# KKK_valdiklis.net
KiCad netlist of a schematic drawn in EAGLE
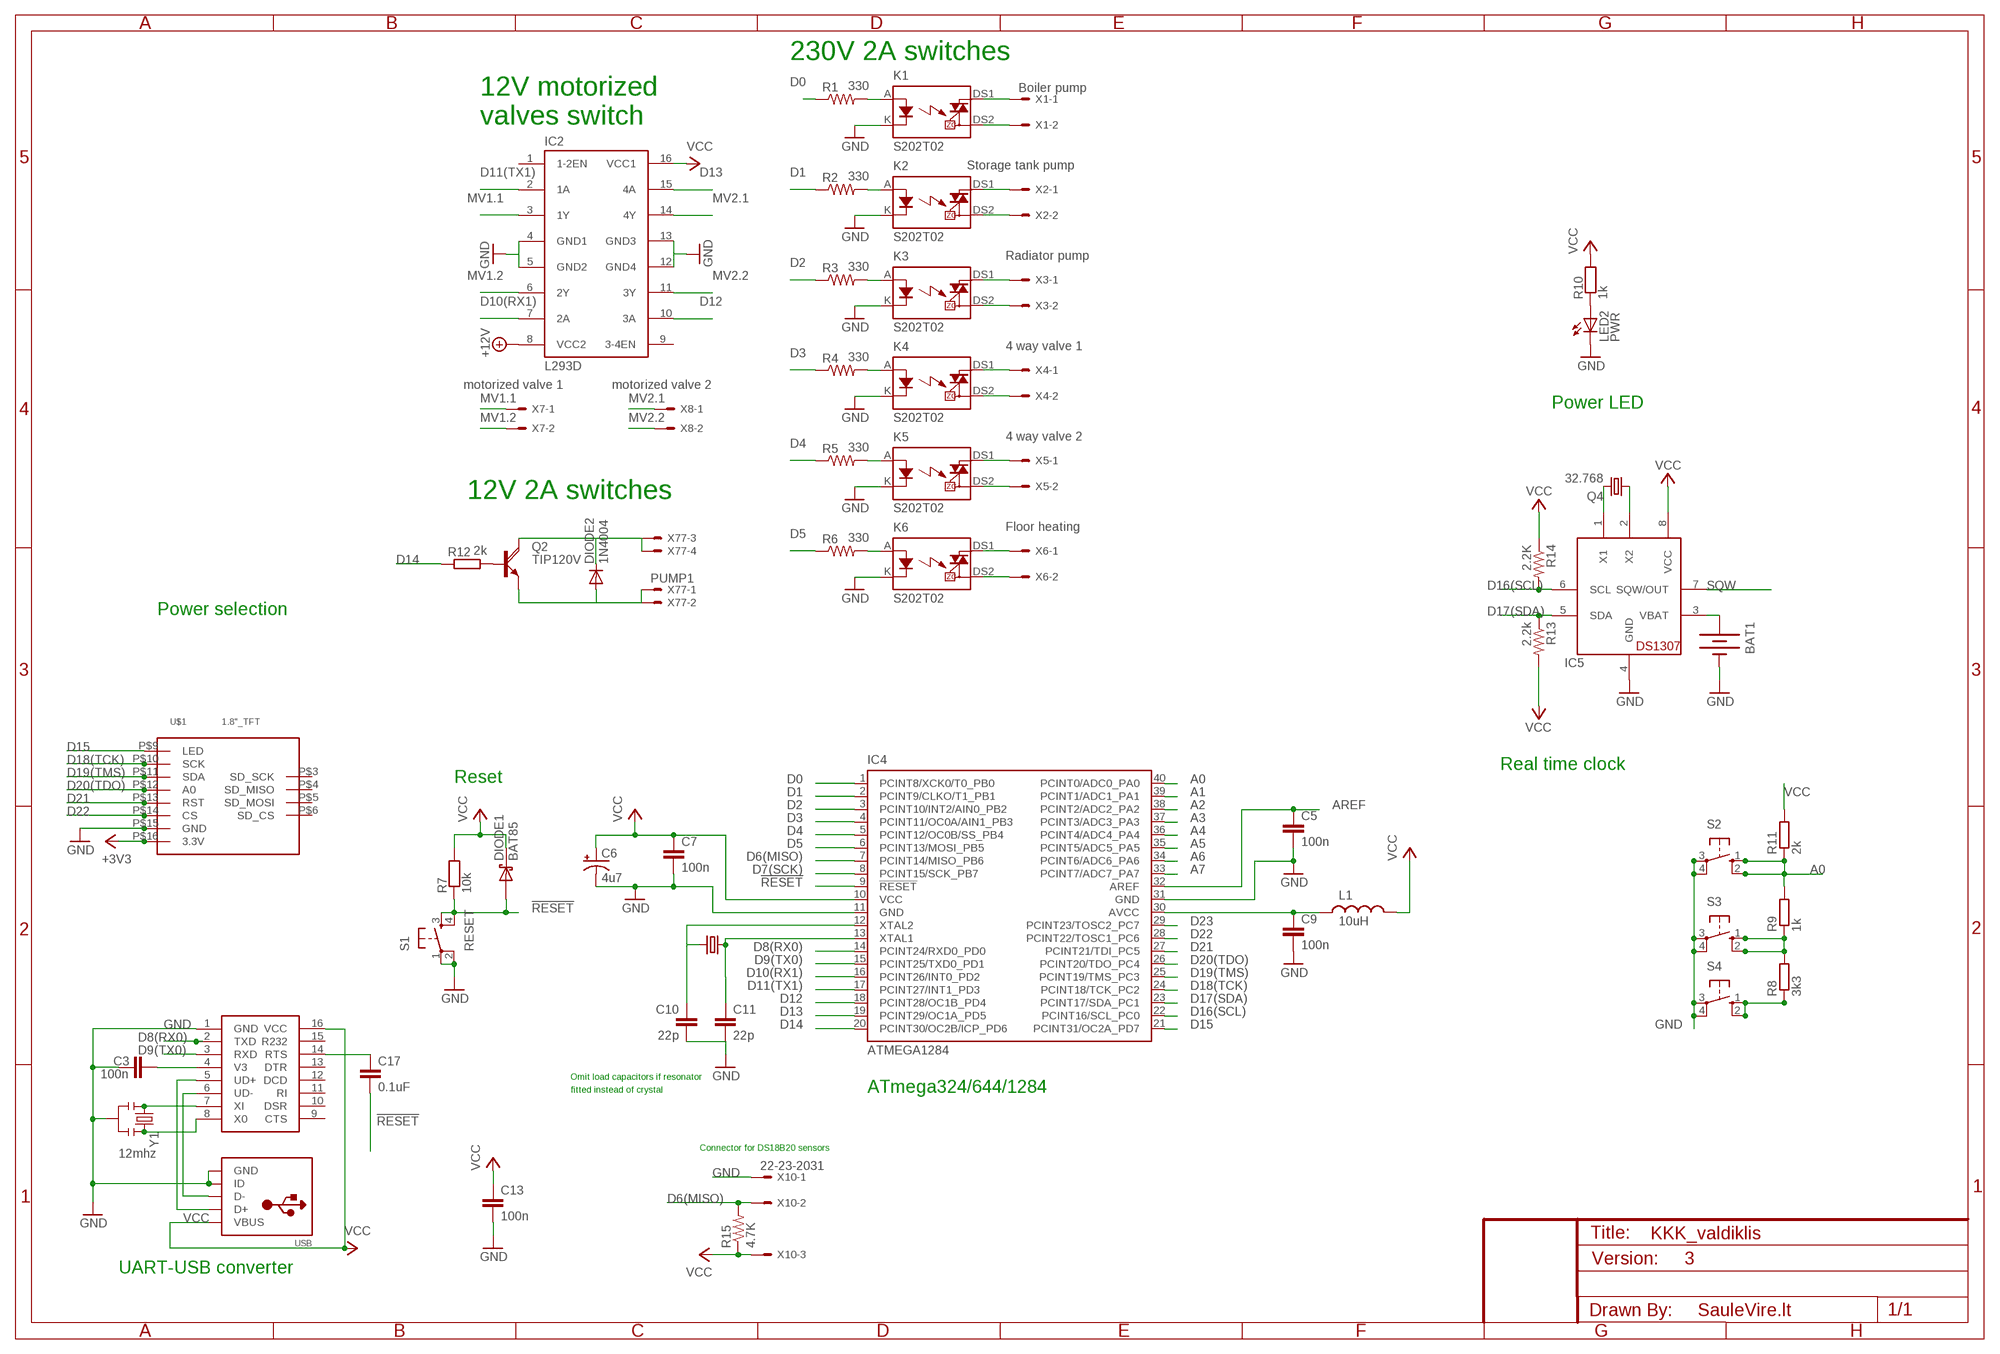
[diagram p0: schematic, sheet 1]

(export (version "E")
  (design (tool "Eeschema 10.0.6"))
  (components
    (comp (ref "BAT1")
      (value "BATTERY20PTH")
      (footprint "eagle-import:BATTCOM_20MM_PTH")
      (libsource (lib "eagle-import") (part "BATTERY20PTH"))
    )
    (comp (ref "C3")
      (value "100n")
      (footprint "eagle-import:CAP-PTH-SMALL")
      (libsource (lib "eagle-import") (part "CAPPTH"))
    )
    (comp (ref "C5")
      (value "100n")
      (footprint "eagle-import:CAP-PTH-SMALL")
      (libsource (lib "eagle-import") (part "CAPPTH"))
    )
    (comp (ref "C6")
      (value "4u7")
      (footprint "eagle-import:CPOL-RADIAL-10UF-25V")
      (libsource (lib "eagle-import") (part "CAP_POLPTH2"))
    )
    (comp (ref "C7")
      (value "100n")
      (footprint "eagle-import:CAP-PTH-SMALL")
      (libsource (lib "eagle-import") (part "CAPPTH"))
    )
    (comp (ref "C9")
      (value "100n")
      (footprint "eagle-import:CAP-PTH-SMALL")
      (libsource (lib "eagle-import") (part "CAPPTH"))
    )
    (comp (ref "C10")
      (value "22p")
      (footprint "eagle-import:CAP-PTH-SMALL")
      (libsource (lib "eagle-import") (part "CAPPTH"))
    )
    (comp (ref "C11")
      (value "22p")
      (footprint "eagle-import:CAP-PTH-SMALL")
      (libsource (lib "eagle-import") (part "CAPPTH"))
    )
    (comp (ref "C13")
      (value "100n")
      (footprint "eagle-import:CAP-PTH-SMALL")
      (libsource (lib "eagle-import") (part "CAPPTH"))
    )
    (comp (ref "C17")
      (value "0.1uF")
      (footprint "eagle-import:C025-024X044")
      (libsource (lib "eagle-import") (part "C-EU025-024X044"))
    )
    (comp (ref "DIODE1")
      (value "BAT85")
      (footprint "eagle-import:DIODE-TH-0.4")
      (libsource (lib "eagle-import") (part "DIODE-SCHOTTKY"))
    )
    (comp (ref "DIODE2")
      (value "1N4004")
      (footprint "eagle-import:DO41-10")
      (libsource (lib "eagle-import") (part "1N4004"))
    )
    (comp (ref "IC2")
      (value "L293D")
      (footprint "eagle-import:DIL16")
      (libsource (lib "eagle-import") (part "L293D"))
    )
    (comp (ref "IC4")
      (value "ATMEGA1284")
      (footprint "eagle-import:DIL40")
      (fields (field (name "MPN") "ATMEGA644-20PU"))
      (libsource (lib "eagle-import") (part "ATMEGA644-PU20"))
    )
    (comp (ref "IC5")
      (value "DS1307")
      (footprint "eagle-import:DIL08")
      (libsource (lib "eagle-import") (part "DS1307"))
    )
    (comp (ref "K1")
      (value "S202T02")
      (footprint "eagle-import:S202T02")
      (libsource (lib "eagle-import") (part "S202T02"))
    )
    (comp (ref "K2")
      (value "S202T02")
      (footprint "eagle-import:S202T02")
      (libsource (lib "eagle-import") (part "S202T02"))
    )
    (comp (ref "K3")
      (value "S202T02")
      (footprint "eagle-import:S202T02")
      (libsource (lib "eagle-import") (part "S202T02"))
    )
    (comp (ref "K4")
      (value "S202T02")
      (footprint "eagle-import:S202T02")
      (libsource (lib "eagle-import") (part "S202T02"))
    )
    (comp (ref "K5")
      (value "S202T02")
      (footprint "eagle-import:S202T02")
      (libsource (lib "eagle-import") (part "S202T02"))
    )
    (comp (ref "K6")
      (value "S202T02")
      (footprint "eagle-import:S202T02")
      (libsource (lib "eagle-import") (part "S202T02"))
    )
    (comp (ref "L1")
      (value "10uH")
      (footprint "eagle-import:RES-AXIAL-0.4")
      (libsource (lib "eagle-import") (part "INDUCTOR0.4{dblquote}-AXIAL"))
    )
    (comp (ref "LED2")
      (value "PWR")
      (footprint "eagle-import:LED3MM")
      (libsource (lib "eagle-import") (part "LED3MM"))
    )
    (comp (ref "Q2")
      (value "TIP120V")
      (footprint "eagle-import:TO220AV")
      (libsource (lib "eagle-import") (part "TIP120V"))
    )
    (comp (ref "Q4")
      (value "32.768")
      (footprint "eagle-import:TC38H")
      (libsource (lib "eagle-import") (part "CRYTALTC38H"))
    )
    (comp (ref "R1")
      (value "330")
      (footprint "eagle-import:0207_10")
      (libsource (lib "eagle-import") (part "resistor-1_R-US_0207/10"))
    )
    (comp (ref "R2")
      (value "330")
      (footprint "eagle-import:0207_10")
      (libsource (lib "eagle-import") (part "resistor-1_R-US_0207/10"))
    )
    (comp (ref "R3")
      (value "330")
      (footprint "eagle-import:0207_10")
      (libsource (lib "eagle-import") (part "resistor-1_R-US_0207/10"))
    )
    (comp (ref "R4")
      (value "330")
      (footprint "eagle-import:0207_10")
      (libsource (lib "eagle-import") (part "resistor-1_R-US_0207/10"))
    )
    (comp (ref "R5")
      (value "330")
      (footprint "eagle-import:0207_10")
      (libsource (lib "eagle-import") (part "resistor-1_R-US_0207/10"))
    )
    (comp (ref "R6")
      (value "330")
      (footprint "eagle-import:0207_10")
      (libsource (lib "eagle-import") (part "resistor-1_R-US_0207/10"))
    )
    (comp (ref "R7")
      (value "10k")
      (footprint "eagle-import:RES-AXIAL-0.4")
      (libsource (lib "eagle-import") (part "RESISTOR"))
    )
    (comp (ref "R8")
      (value "3k3")
      (footprint "eagle-import:0207_10")
      (libsource (lib "eagle-import") (part "R-EU_0207/10"))
    )
    (comp (ref "R9")
      (value "1k")
      (footprint "eagle-import:0207_10")
      (libsource (lib "eagle-import") (part "R-EU_0207/10"))
    )
    (comp (ref "R10")
      (value "1k")
      (footprint "eagle-import:RES-AXIAL-0.4")
      (libsource (lib "eagle-import") (part "RESISTOR"))
    )
    (comp (ref "R11")
      (value "2k")
      (footprint "eagle-import:0207_10")
      (libsource (lib "eagle-import") (part "R-EU_0207/10"))
    )
    (comp (ref "R12")
      (value "2k")
      (footprint "eagle-import:0207_10")
      (libsource (lib "eagle-import") (part "R-EU_0207/10"))
    )
    (comp (ref "R13")
      (value "2.2k")
      (footprint "eagle-import:0207_10")
      (libsource (lib "eagle-import") (part "R-US_0207/10"))
    )
    (comp (ref "R14")
      (value "2.2K")
      (footprint "eagle-import:0207_10")
      (libsource (lib "eagle-import") (part "R-US_0207/10"))
    )
    (comp (ref "R15")
      (value "4.7K")
      (footprint "eagle-import:0207_10")
      (libsource (lib "eagle-import") (part "R-US_0207/10"))
    )
    (comp (ref "S1")
      (value "RESET")
      (footprint "eagle-import:TACTILE-PTH")
      (libsource (lib "eagle-import") (part "TAC_SWITCHPTH"))
    )
    (comp (ref "S2")
      (value "10-XX")
      (footprint "eagle-import:B3F-10XX")
      (fields (field (name "MPN") "B3F-1000"))
      (libsource (lib "eagle-import") (part "10-XX"))
    )
    (comp (ref "S3")
      (value "10-XX")
      (footprint "eagle-import:B3F-10XX")
      (fields (field (name "MPN") "B3F-1000"))
      (libsource (lib "eagle-import") (part "10-XX"))
    )
    (comp (ref "S4")
      (value "10-XX")
      (footprint "eagle-import:B3F-10XX")
      (fields (field (name "MPN") "B3F-1000"))
      (libsource (lib "eagle-import") (part "10-XX"))
    )
    (comp (ref "U$1")
      (value "1.8\"_TFT")
      (footprint "eagle-import:1.8__TFT")
      (libsource (lib "eagle-import") (part "1.8{dblquote}_TFT"))
    )
    (comp (ref "U$2")
      (value "CH340G")
      (footprint "eagle-import:SO016")
      (libsource (lib "eagle-import") (part "CH340G"))
    )
    (comp (ref "USB")
      (value "USBMOLEX")
      (footprint "eagle-import:USB-MINIB-THM-MOLEX")
      (libsource (lib "eagle-import") (part "USBMOLEX"))
    )
    (comp (ref "X1")
      (value "Boiler pump")
      (footprint "eagle-import:22-23-2021")
      (fields (field (name "MF") "MOLEX") (field (name "MPN") "22-23-2021"))
      (libsource (lib "eagle-import") (part "22-23-2021"))
    )
    (comp (ref "X2")
      (value "Storage tank pump")
      (footprint "eagle-import:22-23-2021")
      (fields (field (name "MF") "MOLEX") (field (name "MPN") "22-23-2021"))
      (libsource (lib "eagle-import") (part "22-23-2021"))
    )
    (comp (ref "X3")
      (value "Radiator pump")
      (footprint "eagle-import:22-23-2021")
      (fields (field (name "MF") "MOLEX") (field (name "MPN") "22-23-2021"))
      (libsource (lib "eagle-import") (part "22-23-2021"))
    )
    (comp (ref "X4")
      (value "4 way valve 1")
      (footprint "eagle-import:22-23-2021")
      (fields (field (name "MF") "MOLEX") (field (name "MPN") "22-23-2021"))
      (libsource (lib "eagle-import") (part "22-23-2021"))
    )
    (comp (ref "X5")
      (value "4 way valve 2")
      (footprint "eagle-import:22-23-2021")
      (fields (field (name "MF") "MOLEX") (field (name "MPN") "22-23-2021"))
      (libsource (lib "eagle-import") (part "22-23-2021"))
    )
    (comp (ref "X6")
      (value "Floor heating")
      (footprint "eagle-import:22-23-2021")
      (fields (field (name "MF") "MOLEX") (field (name "MPN") "22-23-2021"))
      (libsource (lib "eagle-import") (part "22-23-2021"))
    )
    (comp (ref "X7")
      (value "motorized valve 1")
      (footprint "eagle-import:22-23-2021")
      (fields (field (name "MF") "MOLEX") (field (name "MPN") "22-23-2021"))
      (libsource (lib "eagle-import") (part "22-23-2021"))
    )
    (comp (ref "X8")
      (value "motorized valve 2")
      (footprint "eagle-import:22-23-2021")
      (fields (field (name "MF") "MOLEX") (field (name "MPN") "22-23-2021"))
      (libsource (lib "eagle-import") (part "22-23-2021"))
    )
    (comp (ref "X9")
      (value "16MHz")
      (footprint "eagle-import:HC49US")
      (libsource (lib "eagle-import") (part "CRYSTALHC49US"))
    )
    (comp (ref "X10")
      (value "22-23-2031")
      (footprint "eagle-import:22-23-2031")
      (fields (field (name "MF") "MOLEX"))
      (libsource (lib "eagle-import") (part "22-23-2031"))
    )
    (comp (ref "X77")
      (value "PUMP1")
      (footprint "eagle-import:22-23-2041")
      (fields (field (name "MF") "MOLEX") (field (name "MPN") "22-23-2041"))
      (libsource (lib "eagle-import") (part "22-23-2041"))
    )
    (comp (ref "Y1")
      (value "12mhz")
      (footprint "eagle-import:RESONATOR-PTH")
      (libsource (lib "eagle-import") (part "RESONATORPTH"))
    )
  )
  (nets
    (net (code "1") (name "+3V3") (class "Default")
      (node (ref "U$1") (pin "P$16") (pinfunction "3.3V_P$16") (pintype "bidirectional"))
    )
    (net (code "2") (name "+12V") (class "Default")
      (node (ref "IC2") (pin "8") (pinfunction "VCC2_8") (pintype "power_in"))
    )
    (net (code "3") (name "/A0") (class "Default")
      (node (ref "IC4") (pin "40") (pinfunction "PCINT0/ADC0_PA0_40") (pintype "bidirectional"))
      (node (ref "R11") (pin "1") (pinfunction "1_1") (pintype "passive"))
      (node (ref "R9") (pin "2") (pinfunction "2_2") (pintype "passive"))
      (node (ref "S2") (pin "1") (pinfunction "S_1") (pintype "passive"))
      (node (ref "S2") (pin "2") (pinfunction "S1_2") (pintype "passive"))
    )
    (net (code "4") (name "/A1") (class "Default")
      (node (ref "IC4") (pin "39") (pinfunction "PCINT1/ADC1_PA1_39") (pintype "bidirectional"))
    )
    (net (code "5") (name "/A2") (class "Default")
      (node (ref "IC4") (pin "38") (pinfunction "PCINT2/ADC2_PA2_38") (pintype "bidirectional"))
    )
    (net (code "6") (name "/A3") (class "Default")
      (node (ref "IC4") (pin "37") (pinfunction "PCINT3/ADC3_PA3_37") (pintype "bidirectional"))
    )
    (net (code "7") (name "/A4") (class "Default")
      (node (ref "IC4") (pin "36") (pinfunction "PCINT4/ADC4_PA4_36") (pintype "bidirectional"))
    )
    (net (code "8") (name "/A5") (class "Default")
      (node (ref "IC4") (pin "35") (pinfunction "PCINT5/ADC5_PA5_35") (pintype "bidirectional"))
    )
    (net (code "9") (name "/A6") (class "Default")
      (node (ref "IC4") (pin "34") (pinfunction "PCINT6/ADC6_PA6_34") (pintype "bidirectional"))
    )
    (net (code "10") (name "/A7") (class "Default")
      (node (ref "IC4") (pin "33") (pinfunction "PCINT7/ADC7_PA7_33") (pintype "bidirectional"))
    )
    (net (code "11") (name "/AREF") (class "Default")
      (node (ref "C5") (pin "1") (pinfunction "1_1") (pintype "passive"))
      (node (ref "IC4") (pin "32") (pinfunction "AREF_32") (pintype "passive"))
    )
    (net (code "12") (name "/D0") (class "Default")
      (node (ref "IC4") (pin "1") (pinfunction "PCINT8/XCK0/T0_PB0_1") (pintype "bidirectional"))
      (node (ref "R1") (pin "1") (pinfunction "1_1") (pintype "passive"))
    )
    (net (code "13") (name "/D1") (class "Default")
      (node (ref "IC4") (pin "2") (pinfunction "PCINT9/CLKO/T1_PB1_2") (pintype "bidirectional"))
      (node (ref "R2") (pin "1") (pinfunction "1_1") (pintype "passive"))
    )
    (net (code "14") (name "/D2") (class "Default")
      (node (ref "IC4") (pin "3") (pinfunction "PCINT10/INT2/AIN0_PB2_3") (pintype "bidirectional"))
      (node (ref "R3") (pin "1") (pinfunction "1_1") (pintype "passive"))
    )
    (net (code "15") (name "/D3") (class "Default")
      (node (ref "IC4") (pin "4") (pinfunction "PCINT11/OC0A/AIN1_PB3_4") (pintype "bidirectional"))
      (node (ref "R4") (pin "1") (pinfunction "1_1") (pintype "passive"))
    )
    (net (code "16") (name "/D4") (class "Default")
      (node (ref "IC4") (pin "5") (pinfunction "PCINT12/OC0B/SS_PB4_5") (pintype "bidirectional"))
      (node (ref "R5") (pin "1") (pinfunction "1_1") (pintype "passive"))
    )
    (net (code "17") (name "/D5") (class "Default")
      (node (ref "IC4") (pin "6") (pinfunction "PCINT13/MOSI_PB5_6") (pintype "bidirectional"))
      (node (ref "R6") (pin "1") (pinfunction "1_1") (pintype "passive"))
    )
    (net (code "18") (name "/D6(MISO)") (class "Default")
      (node (ref "IC4") (pin "7") (pinfunction "PCINT14/MISO_PB6_7") (pintype "bidirectional"))
      (node (ref "R15") (pin "2") (pinfunction "2_2") (pintype "passive"))
      (node (ref "X10") (pin "2") (pinfunction "S_2") (pintype "passive"))
    )
    (net (code "19") (name "/D7(SCK)") (class "Default")
      (node (ref "IC4") (pin "8") (pinfunction "PCINT15/SCK_PB7_8") (pintype "bidirectional"))
    )
    (net (code "20") (name "/D8(RX0)") (class "Default")
      (node (ref "IC4") (pin "14") (pinfunction "PCINT24/RXD0_PD0_14") (pintype "bidirectional"))
      (node (ref "U$2") (pin "2") (pinfunction "TXD_2") (pintype "bidirectional"))
    )
    (net (code "21") (name "/D9(TX0)") (class "Default")
      (node (ref "IC4") (pin "15") (pinfunction "PCINT25/TXD0_PD1_15") (pintype "bidirectional"))
      (node (ref "U$2") (pin "3") (pinfunction "RXD_3") (pintype "bidirectional"))
    )
    (net (code "22") (name "/D10(RX1)") (class "Default")
      (node (ref "IC2") (pin "7") (pinfunction "2A_7") (pintype "input"))
      (node (ref "IC4") (pin "16") (pinfunction "PCINT26/INT0_PD2_16") (pintype "bidirectional"))
    )
    (net (code "23") (name "/D11(TX1)") (class "Default")
      (node (ref "IC2") (pin "2") (pinfunction "1A_2") (pintype "input"))
      (node (ref "IC4") (pin "17") (pinfunction "PCINT27/INT1_PD3_17") (pintype "bidirectional"))
    )
    (net (code "24") (name "/D12") (class "Default")
      (node (ref "IC2") (pin "10") (pinfunction "3A_10") (pintype "input"))
      (node (ref "IC4") (pin "18") (pinfunction "PCINT28/OC1B_PD4_18") (pintype "bidirectional"))
    )
    (net (code "25") (name "/D13") (class "Default")
      (node (ref "IC2") (pin "15") (pinfunction "4A_15") (pintype "input"))
      (node (ref "IC4") (pin "19") (pinfunction "PCINT29/OC1A_PD5_19") (pintype "bidirectional"))
    )
    (net (code "26") (name "/D14") (class "Default")
      (node (ref "IC4") (pin "20") (pinfunction "PCINT30/OC2B/ICP_PD6_20") (pintype "bidirectional"))
      (node (ref "R12") (pin "1") (pinfunction "1_1") (pintype "passive"))
    )
    (net (code "27") (name "/D15") (class "Default")
      (node (ref "IC4") (pin "21") (pinfunction "PCINT31/OC2A_PD7_21") (pintype "bidirectional"))
      (node (ref "U$1") (pin "P$9") (pinfunction "LED_P$9") (pintype "bidirectional"))
    )
    (net (code "28") (name "/D16(SCL)") (class "Default")
      (node (ref "IC4") (pin "22") (pinfunction "PCINT16/SCL_PC0_22") (pintype "bidirectional"))
      (node (ref "IC5") (pin "6") (pinfunction "SCL_6") (pintype "bidirectional"))
      (node (ref "R14") (pin "2") (pinfunction "2_2") (pintype "passive"))
    )
    (net (code "29") (name "/D17(SDA)") (class "Default")
      (node (ref "IC4") (pin "23") (pinfunction "PCINT17/SDA_PC1_23") (pintype "bidirectional"))
      (node (ref "IC5") (pin "5") (pinfunction "SDA_5") (pintype "bidirectional"))
      (node (ref "R13") (pin "1") (pinfunction "1_1") (pintype "passive"))
    )
    (net (code "30") (name "/D18(TCK)") (class "Default")
      (node (ref "IC4") (pin "24") (pinfunction "PCINT18/TCK_PC2_24") (pintype "bidirectional"))
      (node (ref "U$1") (pin "P$10") (pinfunction "SCK_P$10") (pintype "bidirectional"))
    )
    (net (code "31") (name "/D19(TMS)") (class "Default")
      (node (ref "IC4") (pin "25") (pinfunction "PCINT19/TMS_PC3_25") (pintype "bidirectional"))
      (node (ref "U$1") (pin "P$11") (pinfunction "SDA_P$11") (pintype "bidirectional"))
    )
    (net (code "32") (name "/D20(TDO)") (class "Default")
      (node (ref "IC4") (pin "26") (pinfunction "PCINT20/TDO_PC4_26") (pintype "bidirectional"))
      (node (ref "U$1") (pin "P$12") (pinfunction "A0_P$12") (pintype "bidirectional"))
    )
    (net (code "33") (name "/D21") (class "Default")
      (node (ref "IC4") (pin "27") (pinfunction "PCINT21/TDI_PC5_27") (pintype "bidirectional"))
      (node (ref "U$1") (pin "P$13") (pinfunction "RST_P$13") (pintype "bidirectional"))
    )
    (net (code "34") (name "/D22") (class "Default")
      (node (ref "IC4") (pin "28") (pinfunction "PCINT22/TOSC1_PC6_28") (pintype "bidirectional"))
      (node (ref "U$1") (pin "P$14") (pinfunction "CS_P$14") (pintype "bidirectional"))
    )
    (net (code "35") (name "/D23") (class "Default")
      (node (ref "IC4") (pin "29") (pinfunction "PCINT23/TOSC2_PC7_29") (pintype "bidirectional"))
    )
    (net (code "36") (name "/MV1.1") (class "Default")
      (node (ref "IC2") (pin "3") (pinfunction "1Y_3") (pintype "output"))
      (node (ref "X7") (pin "1") (pinfunction "S_1") (pintype "passive"))
    )
    (net (code "37") (name "/MV1.2") (class "Default")
      (node (ref "IC2") (pin "6") (pinfunction "2Y_6") (pintype "output"))
      (node (ref "X7") (pin "2") (pinfunction "S_2") (pintype "passive"))
    )
    (net (code "38") (name "/MV2.1") (class "Default")
      (node (ref "IC2") (pin "14") (pinfunction "4Y_14") (pintype "output"))
      (node (ref "X8") (pin "1") (pinfunction "S_1") (pintype "passive"))
    )
    (net (code "39") (name "/MV2.2") (class "Default")
      (node (ref "IC2") (pin "11") (pinfunction "3Y_11") (pintype "output"))
      (node (ref "X8") (pin "2") (pinfunction "S_2") (pintype "passive"))
    )
    (net (code "40") (name "/SQW") (class "Default")
      (node (ref "IC5") (pin "7") (pinfunction "SQW/OUT_7") (pintype "bidirectional"))
    )
    (net (code "41") (name "/~{RESET}") (class "Default")
      (node (ref "C17") (pin "2") (pinfunction "2_2") (pintype "passive"))
      (node (ref "DIODE1") (pin "A") (pinfunction "A_A") (pintype "passive"))
      (node (ref "IC4") (pin "9") (pinfunction "~{RESET}_9") (pintype "input"))
      (node (ref "R7") (pin "P$1") (pinfunction "1_P$1") (pintype "passive"))
      (node (ref "S1") (pin "3") (pinfunction "3_3") (pintype "passive"))
      (node (ref "S1") (pin "4") (pinfunction "4_4") (pintype "passive"))
    )
    (net (code "42") (name "GND") (class "Default")
      (node (ref "BAT1") (pin "2") (pinfunction "-_2") (pintype "power_in"))
      (node (ref "C10") (pin "2") (pinfunction "2_2") (pintype "passive"))
      (node (ref "C11") (pin "2") (pinfunction "2_2") (pintype "passive"))
      (node (ref "C13") (pin "2") (pinfunction "2_2") (pintype "passive"))
      (node (ref "C3") (pin "1") (pinfunction "1_1") (pintype "passive"))
      (node (ref "C5") (pin "2") (pinfunction "2_2") (pintype "passive"))
      (node (ref "C6") (pin "2") (pinfunction "-_2") (pintype "passive"))
      (node (ref "C7") (pin "2") (pinfunction "2_2") (pintype "passive"))
      (node (ref "C9") (pin "2") (pinfunction "2_2") (pintype "passive"))
      (node (ref "DIODE2") (pin "A") (pinfunction "A_A") (pintype "passive"))
      (node (ref "IC2") (pin "12") (pinfunction "GND4_12") (pintype "power_in"))
      (node (ref "IC2") (pin "13") (pinfunction "GND3_13") (pintype "power_in"))
      (node (ref "IC2") (pin "4") (pinfunction "GND1_4") (pintype "power_in"))
      (node (ref "IC2") (pin "5") (pinfunction "GND2_5") (pintype "power_in"))
      (node (ref "IC4") (pin "11") (pinfunction "GND_11") (pintype "power_in"))
      (node (ref "IC4") (pin "31") (pinfunction "GND_31") (pintype "power_in"))
      (node (ref "IC5") (pin "4") (pinfunction "GND_4") (pintype "power_in"))
      (node (ref "K1") (pin "K") (pinfunction "K_K") (pintype "passive"))
      (node (ref "K2") (pin "K") (pinfunction "K_K") (pintype "passive"))
      (node (ref "K3") (pin "K") (pinfunction "K_K") (pintype "passive"))
      (node (ref "K4") (pin "K") (pinfunction "K_K") (pintype "passive"))
      (node (ref "K5") (pin "K") (pinfunction "K_K") (pintype "passive"))
      (node (ref "K6") (pin "K") (pinfunction "K_K") (pintype "passive"))
      (node (ref "LED2") (pin "K") (pinfunction "C_K") (pintype "passive"))
      (node (ref "Q2") (pin "E") (pinfunction "E_E") (pintype "passive"))
      (node (ref "S1") (pin "1") (pinfunction "1_1") (pintype "passive"))
      (node (ref "S1") (pin "2") (pinfunction "2_2") (pintype "passive"))
      (node (ref "S2") (pin "3") (pinfunction "P_3") (pintype "passive"))
      (node (ref "S2") (pin "4") (pinfunction "P1_4") (pintype "passive"))
      (node (ref "S3") (pin "3") (pinfunction "P_3") (pintype "passive"))
      (node (ref "S3") (pin "4") (pinfunction "P1_4") (pintype "passive"))
      (node (ref "S4") (pin "3") (pinfunction "P_3") (pintype "passive"))
      (node (ref "S4") (pin "4") (pinfunction "P1_4") (pintype "passive"))
      (node (ref "U$1") (pin "P$15") (pinfunction "GND_P$15") (pintype "bidirectional"))
      (node (ref "U$2") (pin "1") (pinfunction "GND_1") (pintype "bidirectional"))
      (node (ref "USB") (pin "GND") (pinfunction "GND_GND") (pintype "power_in"))
      (node (ref "USB") (pin "ID") (pinfunction "ID_ID") (pintype "bidirectional"))
      (node (ref "X10") (pin "1") (pinfunction "S_1") (pintype "passive"))
      (node (ref "X77") (pin "1") (pinfunction "S_1") (pintype "passive"))
      (node (ref "X77") (pin "2") (pinfunction "S_2") (pintype "passive"))
      (node (ref "Y1") (pin "2") (pinfunction "2_2") (pintype "passive"))
    )
    (net (code "43") (name "Net-(BAT1-+)") (class "Default")
      (node (ref "BAT1") (pin "1") (pinfunction "+_1") (pintype "power_in"))
      (node (ref "IC5") (pin "3") (pinfunction "VBAT_3") (pintype "power_in"))
    )
    (net (code "44") (name "Net-(IC4-AVCC)") (class "Default")
      (node (ref "C9") (pin "1") (pinfunction "1_1") (pintype "passive"))
      (node (ref "IC4") (pin "30") (pinfunction "AVCC_30") (pintype "power_in"))
      (node (ref "L1") (pin "P$1") (pinfunction "1_P$1") (pintype "passive"))
    )
    (net (code "45") (name "Net-(IC4-XTAL1)") (class "Default")
      (node (ref "C11") (pin "1") (pinfunction "1_1") (pintype "passive"))
      (node (ref "IC4") (pin "13") (pinfunction "XTAL1_13") (pintype "input"))
      (node (ref "X9") (pin "1") (pinfunction "1_1") (pintype "passive"))
    )
    (net (code "46") (name "Net-(IC4-XTAL2)") (class "Default")
      (node (ref "C10") (pin "1") (pinfunction "1_1") (pintype "passive"))
      (node (ref "IC4") (pin "12") (pinfunction "XTAL2_12") (pintype "output"))
      (node (ref "X9") (pin "2") (pinfunction "2_2") (pintype "passive"))
    )
    (net (code "47") (name "Net-(IC5-X1)") (class "Default")
      (node (ref "IC5") (pin "1") (pinfunction "X1_1") (pintype "passive"))
      (node (ref "Q4") (pin "2") (pinfunction "2_2") (pintype "passive"))
    )
    (net (code "48") (name "Net-(IC5-X2)") (class "Default")
      (node (ref "IC5") (pin "2") (pinfunction "X2_2") (pintype "passive"))
      (node (ref "Q4") (pin "1") (pinfunction "1_1") (pintype "passive"))
    )
    (net (code "49") (name "Net-(K1-PadA)") (class "Default")
      (node (ref "K1") (pin "A") (pinfunction "A_A") (pintype "passive"))
      (node (ref "R1") (pin "2") (pinfunction "2_2") (pintype "passive"))
    )
    (net (code "50") (name "Net-(K2-PadA)") (class "Default")
      (node (ref "K2") (pin "A") (pinfunction "A_A") (pintype "passive"))
      (node (ref "R2") (pin "2") (pinfunction "2_2") (pintype "passive"))
    )
    (net (code "51") (name "Net-(K3-PadA)") (class "Default")
      (node (ref "K3") (pin "A") (pinfunction "A_A") (pintype "passive"))
      (node (ref "R3") (pin "2") (pinfunction "2_2") (pintype "passive"))
    )
    (net (code "52") (name "Net-(K4-PadA)") (class "Default")
      (node (ref "K4") (pin "A") (pinfunction "A_A") (pintype "passive"))
      (node (ref "R4") (pin "2") (pinfunction "2_2") (pintype "passive"))
    )
    (net (code "53") (name "Net-(K5-PadA)") (class "Default")
      (node (ref "K5") (pin "A") (pinfunction "A_A") (pintype "passive"))
      (node (ref "R5") (pin "2") (pinfunction "2_2") (pintype "passive"))
    )
    (net (code "54") (name "Net-(K6-PadA)") (class "Default")
      (node (ref "K6") (pin "A") (pinfunction "A_A") (pintype "passive"))
      (node (ref "R6") (pin "2") (pinfunction "2_2") (pintype "passive"))
    )
    (net (code "55") (name "Net-(Q2-PadB)") (class "Default")
      (node (ref "Q2") (pin "B") (pinfunction "B_B") (pintype "passive"))
      (node (ref "R12") (pin "2") (pinfunction "2_2") (pintype "passive"))
    )
    (net (code "56") (name "Net-(R10-1)") (class "Default")
      (node (ref "LED2") (pin "A") (pinfunction "A_A") (pintype "passive"))
      (node (ref "R10") (pin "P$1") (pinfunction "1_P$1") (pintype "passive"))
    )
    (net (code "57") (name "Net-(S3-S)") (class "Default")
      (node (ref "R8") (pin "2") (pinfunction "2_2") (pintype "passive"))
      (node (ref "R9") (pin "1") (pinfunction "1_1") (pintype "passive"))
      (node (ref "S3") (pin "1") (pinfunction "S_1") (pintype "passive"))
      (node (ref "S3") (pin "2") (pinfunction "S1_2") (pintype "passive"))
    )
    (net (code "58") (name "Net-(S4-S)") (class "Default")
      (node (ref "R8") (pin "1") (pinfunction "1_1") (pintype "passive"))
      (node (ref "S4") (pin "1") (pinfunction "S_1") (pintype "passive"))
      (node (ref "S4") (pin "2") (pinfunction "S1_2") (pintype "passive"))
    )
    (net (code "59") (name "Net-(U$2-RTS)") (class "Default")
      (node (ref "C17") (pin "1") (pinfunction "1_1") (pintype "passive"))
      (node (ref "U$2") (pin "14") (pinfunction "RTS_14") (pintype "bidirectional"))
    )
    (net (code "60") (name "Net-(U$2-UD+)") (class "Default")
      (node (ref "U$2") (pin "5") (pinfunction "UD+_5") (pintype "bidirectional"))
      (node (ref "USB") (pin "D+") (pinfunction "D+_D+") (pintype "bidirectional"))
    )
    (net (code "61") (name "Net-(U$2-UD-)") (class "Default")
      (node (ref "U$2") (pin "6") (pinfunction "UD-_6") (pintype "bidirectional"))
      (node (ref "USB") (pin "D-") (pinfunction "D-_D-") (pintype "bidirectional"))
    )
    (net (code "62") (name "Net-(U$2-V3)") (class "Default")
      (node (ref "C3") (pin "2") (pinfunction "2_2") (pintype "passive"))
      (node (ref "U$2") (pin "4") (pinfunction "V3_4") (pintype "bidirectional"))
    )
    (net (code "63") (name "Net-(U$2-X0)") (class "Default")
      (node (ref "U$2") (pin "8") (pinfunction "X0_8") (pintype "bidirectional"))
      (node (ref "Y1") (pin "3") (pinfunction "3_3") (pintype "passive"))
    )
    (net (code "64") (name "Net-(U$2-XI)") (class "Default")
      (node (ref "U$2") (pin "7") (pinfunction "XI_7") (pintype "bidirectional"))
      (node (ref "Y1") (pin "1") (pinfunction "1_1") (pintype "passive"))
    )
    (net (code "65") (name "Net-(X1A-S)") (class "Default")
      (node (ref "K1") (pin "DS1") (pinfunction "DS1_DS1") (pintype "passive"))
      (node (ref "X1") (pin "1") (pinfunction "S_1") (pintype "passive"))
    )
    (net (code "66") (name "Net-(X1B-S)") (class "Default")
      (node (ref "K1") (pin "DS2") (pinfunction "DS2_DS2") (pintype "passive"))
      (node (ref "X1") (pin "2") (pinfunction "S_2") (pintype "passive"))
    )
    (net (code "67") (name "Net-(X2A-S)") (class "Default")
      (node (ref "K2") (pin "DS1") (pinfunction "DS1_DS1") (pintype "passive"))
      (node (ref "X2") (pin "1") (pinfunction "S_1") (pintype "passive"))
    )
    (net (code "68") (name "Net-(X2B-S)") (class "Default")
      (node (ref "K2") (pin "DS2") (pinfunction "DS2_DS2") (pintype "passive"))
      (node (ref "X2") (pin "2") (pinfunction "S_2") (pintype "passive"))
    )
    (net (code "69") (name "Net-(X3A-S)") (class "Default")
      (node (ref "K3") (pin "DS1") (pinfunction "DS1_DS1") (pintype "passive"))
      (node (ref "X3") (pin "1") (pinfunction "S_1") (pintype "passive"))
    )
    (net (code "70") (name "Net-(X3B-S)") (class "Default")
      (node (ref "K3") (pin "DS2") (pinfunction "DS2_DS2") (pintype "passive"))
      (node (ref "X3") (pin "2") (pinfunction "S_2") (pintype "passive"))
    )
    (net (code "71") (name "Net-(X4A-S)") (class "Default")
      (node (ref "K4") (pin "DS1") (pinfunction "DS1_DS1") (pintype "passive"))
      (node (ref "X4") (pin "1") (pinfunction "S_1") (pintype "passive"))
    )
    (net (code "72") (name "Net-(X4B-S)") (class "Default")
      (node (ref "K4") (pin "DS2") (pinfunction "DS2_DS2") (pintype "passive"))
      (node (ref "X4") (pin "2") (pinfunction "S_2") (pintype "passive"))
    )
    (net (code "73") (name "Net-(X5A-S)") (class "Default")
      (node (ref "K5") (pin "DS1") (pinfunction "DS1_DS1") (pintype "passive"))
      (node (ref "X5") (pin "1") (pinfunction "S_1") (pintype "passive"))
    )
    (net (code "74") (name "Net-(X5B-S)") (class "Default")
      (node (ref "K5") (pin "DS2") (pinfunction "DS2_DS2") (pintype "passive"))
      (node (ref "X5") (pin "2") (pinfunction "S_2") (pintype "passive"))
    )
    (net (code "75") (name "Net-(X6A-S)") (class "Default")
      (node (ref "K6") (pin "DS1") (pinfunction "DS1_DS1") (pintype "passive"))
      (node (ref "X6") (pin "1") (pinfunction "S_1") (pintype "passive"))
    )
    (net (code "76") (name "Net-(X6B-S)") (class "Default")
      (node (ref "K6") (pin "DS2") (pinfunction "DS2_DS2") (pintype "passive"))
      (node (ref "X6") (pin "2") (pinfunction "S_2") (pintype "passive"))
    )
    (net (code "77") (name "Net-(X77C-S)") (class "Default")
      (node (ref "DIODE2") (pin "C") (pinfunction "C_C") (pintype "passive"))
      (node (ref "Q2") (pin "C") (pinfunction "C_C") (pintype "passive"))
      (node (ref "X77") (pin "3") (pinfunction "S_3") (pintype "passive"))
      (node (ref "X77") (pin "4") (pinfunction "S_4") (pintype "passive"))
    )
    (net (code "78") (name "VCC") (class "Default")
      (node (ref "C13") (pin "1") (pinfunction "1_1") (pintype "passive"))
      (node (ref "C6") (pin "1") (pinfunction "+_1") (pintype "passive"))
      (node (ref "C7") (pin "1") (pinfunction "1_1") (pintype "passive"))
      (node (ref "DIODE1") (pin "C") (pinfunction "C_C") (pintype "passive"))
      (node (ref "IC2") (pin "16") (pinfunction "VCC1_16") (pintype "power_in"))
      (node (ref "IC4") (pin "10") (pinfunction "VCC_10") (pintype "power_in"))
      (node (ref "IC5") (pin "8") (pinfunction "VCC_8") (pintype "power_in"))
      (node (ref "L1") (pin "P$2") (pinfunction "2_P$2") (pintype "passive"))
      (node (ref "R10") (pin "P$2") (pinfunction "2_P$2") (pintype "passive"))
      (node (ref "R11") (pin "2") (pinfunction "2_2") (pintype "passive"))
      (node (ref "R13") (pin "2") (pinfunction "2_2") (pintype "passive"))
      (node (ref "R14") (pin "1") (pinfunction "1_1") (pintype "passive"))
      (node (ref "R15") (pin "1") (pinfunction "1_1") (pintype "passive"))
      (node (ref "R7") (pin "P$2") (pinfunction "2_P$2") (pintype "passive"))
      (node (ref "U$2") (pin "16") (pinfunction "VCC_16") (pintype "bidirectional"))
      (node (ref "USB") (pin "VBUS") (pinfunction "VBUS_VBUS") (pintype "power_in"))
      (node (ref "X10") (pin "3") (pinfunction "S_3") (pintype "passive"))
    )
    (net (code "79") (name "unconnected-(IC2-1-2EN-Pad1)") (class "Default")
      (node (ref "IC2") (pin "1") (pinfunction "1-2EN_1") (pintype "input"))
    )
    (net (code "80") (name "unconnected-(IC2-3-4EN-Pad9)") (class "Default")
      (node (ref "IC2") (pin "9") (pinfunction "3-4EN_9") (pintype "input"))
    )
    (net (code "81") (name "unconnected-(U$1-SD_CS-PadP$6)") (class "Default")
      (node (ref "U$1") (pin "P$6") (pinfunction "SD_CS_P$6") (pintype "bidirectional"))
    )
    (net (code "82") (name "unconnected-(U$1-SD_MISO-PadP$4)") (class "Default")
      (node (ref "U$1") (pin "P$4") (pinfunction "SD_MISO_P$4") (pintype "bidirectional"))
    )
    (net (code "83") (name "unconnected-(U$1-SD_MOSI-PadP$5)") (class "Default")
      (node (ref "U$1") (pin "P$5") (pinfunction "SD_MOSI_P$5") (pintype "bidirectional"))
    )
    (net (code "84") (name "unconnected-(U$1-SD_SCK-PadP$3)") (class "Default")
      (node (ref "U$1") (pin "P$3") (pinfunction "SD_SCK_P$3") (pintype "bidirectional"))
    )
    (net (code "85") (name "unconnected-(U$2-CTS-Pad9)") (class "Default")
      (node (ref "U$2") (pin "9") (pinfunction "CTS_9") (pintype "bidirectional"))
    )
    (net (code "86") (name "unconnected-(U$2-DCD-Pad12)") (class "Default")
      (node (ref "U$2") (pin "12") (pinfunction "DCD_12") (pintype "bidirectional"))
    )
    (net (code "87") (name "unconnected-(U$2-DSR-Pad10)") (class "Default")
      (node (ref "U$2") (pin "10") (pinfunction "DSR_10") (pintype "bidirectional"))
    )
    (net (code "88") (name "unconnected-(U$2-DTR-Pad13)") (class "Default")
      (node (ref "U$2") (pin "13") (pinfunction "DTR_13") (pintype "bidirectional"))
    )
    (net (code "89") (name "unconnected-(U$2-R232-Pad15)") (class "Default")
      (node (ref "U$2") (pin "15") (pinfunction "R232_15") (pintype "bidirectional"))
    )
    (net (code "90") (name "unconnected-(U$2-RI-Pad11)") (class "Default")
      (node (ref "U$2") (pin "11") (pinfunction "RI_11") (pintype "bidirectional"))
    )
  )
)
